# fallBz3.net
KiCad netlist of a schematic drawn in EAGLE
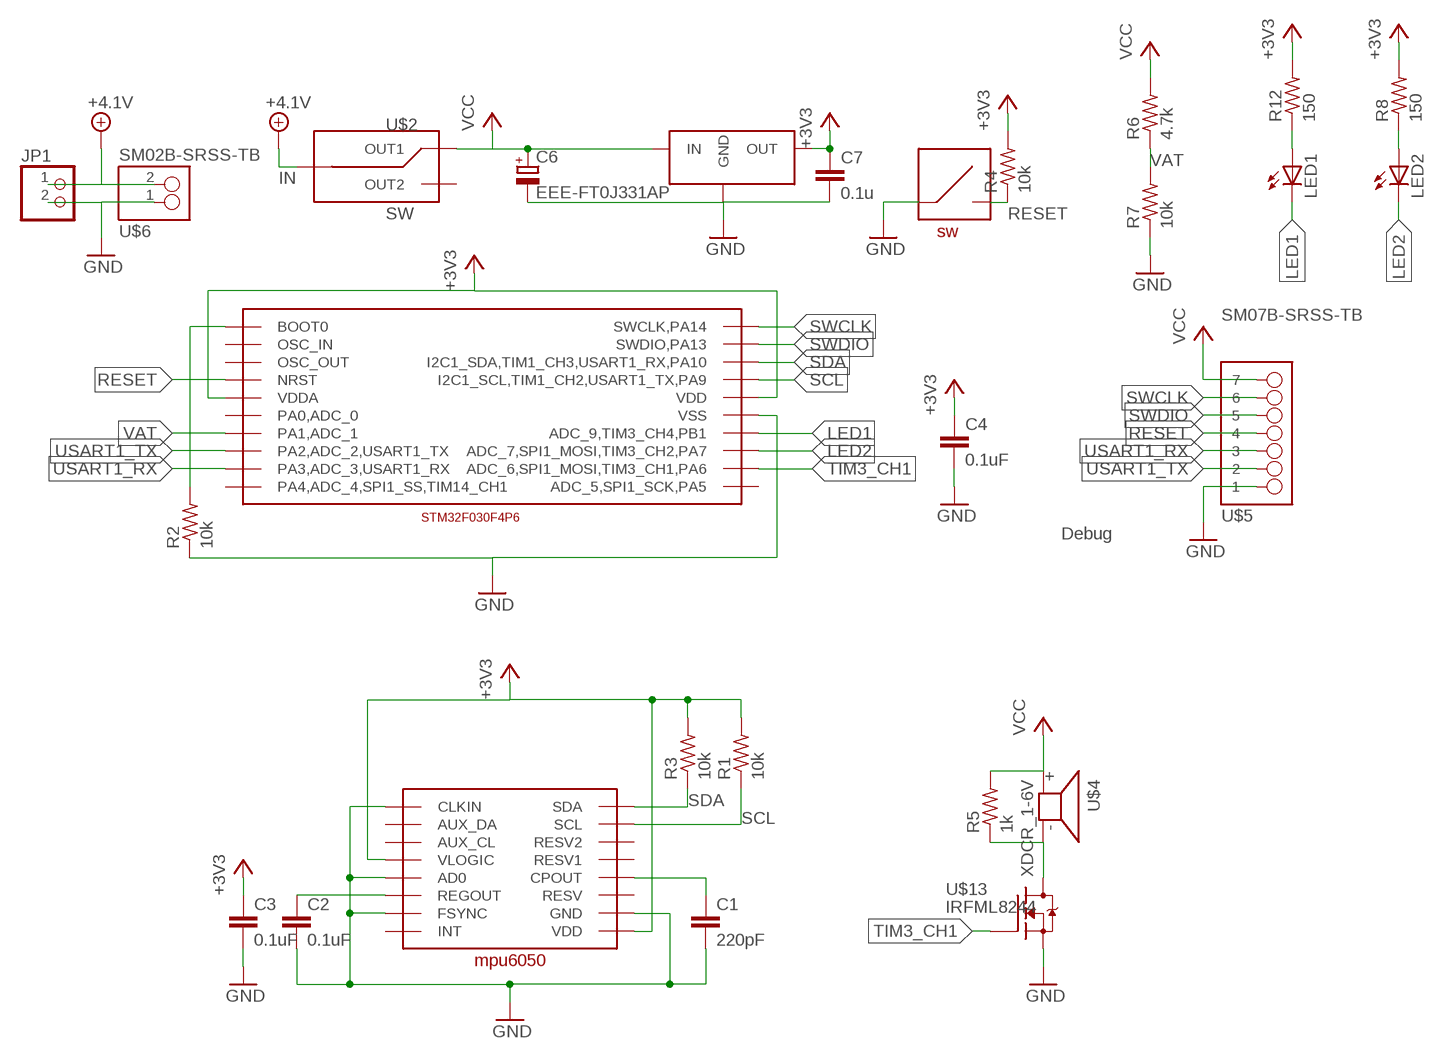
[diagram p0: schematic, sheet 1]

(export (version "E")
  (design (tool "Eeschema 10.0.6"))
  (components
    (comp (ref "C1")
      (value "220pF")
      (footprint "eagle-import:C0603K")
      (libsource (lib "eagle-import") (part "C-EUC0603K"))
    )
    (comp (ref "C2")
      (value "0.1uF")
      (footprint "eagle-import:C0603K")
      (libsource (lib "eagle-import") (part "C-EUC0603K"))
    )
    (comp (ref "C3")
      (value "0.1uF")
      (footprint "eagle-import:C0603K")
      (libsource (lib "eagle-import") (part "C-EUC0603K"))
    )
    (comp (ref "C4")
      (value "0.1uF")
      (footprint "eagle-import:C0603K")
      (libsource (lib "eagle-import") (part "C-EUC0603K"))
    )
    (comp (ref "C6")
      (value "EEE-FT0J331AP")
      (footprint "eagle-import:153CLV-0605")
      (libsource (lib "eagle-import") (part "CPOL-EU153CLV-0605"))
    )
    (comp (ref "C7")
      (value "0.1u")
      (footprint "eagle-import:C0603K")
      (libsource (lib "eagle-import") (part "C-EUC0603K"))
    )
    (comp (ref "JP1")
      (value "PINHD-1X2")
      (footprint "eagle-import:1X02")
      (libsource (lib "eagle-import") (part "PINHD-1X2"))
    )
    (comp (ref "LED1")
      (value "LEDCHIP-LED0603")
      (footprint "eagle-import:CHIP-LED0603")
      (libsource (lib "eagle-import") (part "LEDCHIP-LED0603"))
    )
    (comp (ref "LED2")
      (value "LEDCHIP-LED0603")
      (footprint "eagle-import:CHIP-LED0603")
      (libsource (lib "eagle-import") (part "LEDCHIP-LED0603"))
    )
    (comp (ref "R1")
      (value "10k")
      (footprint "eagle-import:R0603")
      (libsource (lib "eagle-import") (part "R-US_R0603"))
    )
    (comp (ref "R2")
      (value "10k")
      (footprint "eagle-import:R0603")
      (libsource (lib "eagle-import") (part "R-US_R0603"))
    )
    (comp (ref "R3")
      (value "10k")
      (footprint "eagle-import:R0603")
      (libsource (lib "eagle-import") (part "R-US_R0603"))
    )
    (comp (ref "R4")
      (value "10k")
      (footprint "eagle-import:R0603")
      (libsource (lib "eagle-import") (part "R-US_R0603"))
    )
    (comp (ref "R5")
      (value "1k")
      (footprint "eagle-import:R0603")
      (libsource (lib "eagle-import") (part "R-US_R0603"))
    )
    (comp (ref "R6")
      (value "4.7k")
      (footprint "eagle-import:R0603")
      (libsource (lib "eagle-import") (part "R-US_R0603"))
    )
    (comp (ref "R7")
      (value "10k")
      (footprint "eagle-import:R0603")
      (libsource (lib "eagle-import") (part "R-US_R0603"))
    )
    (comp (ref "R8")
      (value "150")
      (footprint "eagle-import:R0603")
      (libsource (lib "eagle-import") (part "R-US_R0603"))
    )
    (comp (ref "R12")
      (value "150")
      (footprint "eagle-import:R0603")
      (libsource (lib "eagle-import") (part "R-US_R0603"))
    )
    (comp (ref "U$1")
      (value "STM-TSSOP20")
      (footprint "eagle-import:STM-TSSOP20")
      (libsource (lib "eagle-import") (part "STM-TSSOP20"))
    )
    (comp (ref "U$2")
      (value "SW")
      (footprint "eagle-import:SS-12D00")
      (libsource (lib "eagle-import") (part "SW"))
    )
    (comp (ref "U$3")
      (value "MPU6050")
      (footprint "eagle-import:MPU6050")
      (libsource (lib "eagle-import") (part "MPU6050"))
    )
    (comp (ref "U$4")
      (value "XDCR_1-6V")
      (footprint "eagle-import:XDCR_1-6V")
      (libsource (lib "eagle-import") (part "XDCR_1-6V"))
    )
    (comp (ref "U$5")
      (value "SM07B-SRSS-TB")
      (footprint "eagle-import:SM07B-SRSS-TB")
      (libsource (lib "eagle-import") (part "SM07B-SRSS-TB"))
    )
    (comp (ref "U$6")
      (value "SM02B-SRSS-TB")
      (footprint "eagle-import:SM02B-SRSS-TB")
      (libsource (lib "eagle-import") (part "SM02B-SRSS-TB"))
    )
    (comp (ref "U$7")
      (value "KMT071-NGJ-LHS")
      (footprint "eagle-import:KMT071-NGJ-LHS")
      (libsource (lib "eagle-import") (part "KMT071-NGJ-LHS"))
    )
    (comp (ref "U$8")
      (value "AP7361-33E")
      (footprint "eagle-import:SOT223")
      (libsource (lib "eagle-import") (part "AP7361-33E"))
    )
    (comp (ref "U$13")
      (value "IRFML8244")
      (footprint "eagle-import:SOT23")
      (libsource (lib "eagle-import") (part "IRFML8244"))
    )
  )
  (nets
    (net (code "1") (name "+3V3") (class "Default")
      (node (ref "C3") (pin "1") (pinfunction "1_1") (pintype "passive"))
      (node (ref "C4") (pin "1") (pinfunction "1_1") (pintype "passive"))
      (node (ref "C7") (pin "1") (pinfunction "1_1") (pintype "passive"))
      (node (ref "R1") (pin "2") (pinfunction "2_2") (pintype "passive"))
      (node (ref "R12") (pin "2") (pinfunction "2_2") (pintype "passive"))
      (node (ref "R3") (pin "2") (pinfunction "2_2") (pintype "passive"))
      (node (ref "R4") (pin "2") (pinfunction "2_2") (pintype "passive"))
      (node (ref "R8") (pin "2") (pinfunction "2_2") (pintype "passive"))
      (node (ref "U$1") (pin "P$16") (pinfunction "VDD_P$16") (pintype "bidirectional"))
      (node (ref "U$1") (pin "P$5") (pinfunction "VDDA_P$5") (pintype "bidirectional"))
      (node (ref "U$3") (pin "VDD") (pinfunction "VDD_VDD") (pintype "bidirectional"))
      (node (ref "U$3") (pin "VLOGIC") (pinfunction "VLOGIC_VLOGIC") (pintype "bidirectional"))
      (node (ref "U$8") (pin "OUT") (pinfunction "OUT_OUT") (pintype "bidirectional"))
    )
    (net (code "2") (name "+4.1V") (class "Default")
      (node (ref "JP1") (pin "1") (pinfunction "1_1") (pintype "passive"))
      (node (ref "U$2") (pin "IN") (pinfunction "IN_IN") (pintype "bidirectional"))
      (node (ref "U$6") (pin "2") (pinfunction "P$2_2") (pintype "bidirectional"))
    )
    (net (code "3") (name "GND") (class "Default")
      (node (ref "C1") (pin "2") (pinfunction "2_2") (pintype "passive"))
      (node (ref "C2") (pin "2") (pinfunction "2_2") (pintype "passive"))
      (node (ref "C3") (pin "2") (pinfunction "2_2") (pintype "passive"))
      (node (ref "C4") (pin "2") (pinfunction "2_2") (pintype "passive"))
      (node (ref "C6") (pin "-") (pinfunction "-_-") (pintype "passive"))
      (node (ref "C7") (pin "2") (pinfunction "2_2") (pintype "passive"))
      (node (ref "JP1") (pin "2") (pinfunction "2_2") (pintype "passive"))
      (node (ref "R2") (pin "1") (pinfunction "1_1") (pintype "passive"))
      (node (ref "R7") (pin "1") (pinfunction "1_1") (pintype "passive"))
      (node (ref "U$1") (pin "P$15") (pinfunction "VSS_P$15") (pintype "bidirectional"))
      (node (ref "U$13") (pin "2") (pinfunction "S_2") (pintype "passive"))
      (node (ref "U$3") (pin "AD0") (pinfunction "AD0_AD0") (pintype "bidirectional"))
      (node (ref "U$3") (pin "CLKIN") (pinfunction "CLKIN_CLKIN") (pintype "bidirectional"))
      (node (ref "U$3") (pin "FSYNC") (pinfunction "FSYNC_FSYNC") (pintype "bidirectional"))
      (node (ref "U$3") (pin "GND") (pinfunction "GND_GND") (pintype "bidirectional"))
      (node (ref "U$5") (pin "P$1") (pinfunction "1_P$1") (pintype "bidirectional"))
      (node (ref "U$6") (pin "1") (pinfunction "P$1_1") (pintype "bidirectional"))
      (node (ref "U$7") (pin "SW0") (pinfunction "P$1_SW0") (pintype "bidirectional"))
      (node (ref "U$7") (pin "SW00") (pinfunction "P$1_SW00") (pintype "bidirectional"))
      (node (ref "U$8") (pin "GND1") (pinfunction "GND_GND1") (pintype "bidirectional"))
      (node (ref "U$8") (pin "GND2") (pinfunction "GND_GND2") (pintype "bidirectional"))
    )
    (net (code "4") (name "LED1") (class "Default")
      (node (ref "LED1") (pin "C") (pinfunction "C_C") (pintype "passive"))
      (node (ref "U$1") (pin "P$14") (pinfunction "ADC_9,TIM3_CH4,PB1_P$14") (pintype "bidirectional"))
    )
    (net (code "5") (name "LED2") (class "Default")
      (node (ref "LED2") (pin "C") (pinfunction "C_C") (pintype "passive"))
      (node (ref "U$1") (pin "P$13") (pinfunction "ADC_7,SPI1_MOSI,TIM3_CH2,PA7_P$13") (pintype "bidirectional"))
    )
    (net (code "6") (name "Net-(C1-Pad1)") (class "Default")
      (node (ref "C1") (pin "1") (pinfunction "1_1") (pintype "passive"))
      (node (ref "U$3") (pin "CPOUT") (pinfunction "CPOUT_CPOUT") (pintype "bidirectional"))
    )
    (net (code "7") (name "Net-(C2-Pad1)") (class "Default")
      (node (ref "C2") (pin "1") (pinfunction "1_1") (pintype "passive"))
      (node (ref "U$3") (pin "REGOUT") (pinfunction "REGOUT_REGOUT") (pintype "bidirectional"))
    )
    (net (code "8") (name "Net-(LED1-PadA)") (class "Default")
      (node (ref "LED1") (pin "A") (pinfunction "A_A") (pintype "passive"))
      (node (ref "R12") (pin "1") (pinfunction "1_1") (pintype "passive"))
    )
    (net (code "9") (name "Net-(LED2-PadA)") (class "Default")
      (node (ref "LED2") (pin "A") (pinfunction "A_A") (pintype "passive"))
      (node (ref "R8") (pin "1") (pinfunction "1_1") (pintype "passive"))
    )
    (net (code "10") (name "Net-(U$1-BOOT0)") (class "Default")
      (node (ref "R2") (pin "2") (pinfunction "2_2") (pintype "passive"))
      (node (ref "U$1") (pin "P$1") (pinfunction "BOOT0_P$1") (pintype "bidirectional"))
    )
    (net (code "11") (name "Net-(U$13-D)") (class "Default")
      (node (ref "R5") (pin "1") (pinfunction "1_1") (pintype "passive"))
      (node (ref "U$13") (pin "3") (pinfunction "D_3") (pintype "passive"))
      (node (ref "U$4") (pin "MINUS") (pinfunction "2_MINUS") (pintype "passive"))
    )
    (net (code "12") (name "RESET") (class "Default")
      (node (ref "R4") (pin "1") (pinfunction "1_1") (pintype "passive"))
      (node (ref "U$1") (pin "P$4") (pinfunction "NRST_P$4") (pintype "bidirectional"))
      (node (ref "U$5") (pin "P$4") (pinfunction "4_P$4") (pintype "bidirectional"))
      (node (ref "U$7") (pin "SW1") (pinfunction "P$2_SW1") (pintype "bidirectional"))
      (node (ref "U$7") (pin "SW11") (pinfunction "P$2_SW11") (pintype "bidirectional"))
    )
    (net (code "13") (name "SCL") (class "Default")
      (node (ref "R1") (pin "1") (pinfunction "1_1") (pintype "passive"))
      (node (ref "U$1") (pin "P$17") (pinfunction "I2C1_SCL,TIM1_CH2,USART1_TX,PA9_P$17") (pintype "bidirectional"))
      (node (ref "U$3") (pin "SCL") (pinfunction "SCL_SCL") (pintype "bidirectional"))
    )
    (net (code "14") (name "SDA") (class "Default")
      (node (ref "R3") (pin "1") (pinfunction "1_1") (pintype "passive"))
      (node (ref "U$1") (pin "P$18") (pinfunction "I2C1_SDA,TIM1_CH3,USART1_RX,PA10_P$18") (pintype "bidirectional"))
      (node (ref "U$3") (pin "SDA") (pinfunction "SDA_SDA") (pintype "bidirectional"))
    )
    (net (code "15") (name "SWCLK") (class "Default")
      (node (ref "U$1") (pin "P$20") (pinfunction "SWCLK,PA14_P$20") (pintype "bidirectional"))
      (node (ref "U$5") (pin "P$6") (pinfunction "6_P$6") (pintype "bidirectional"))
    )
    (net (code "16") (name "SWDIO") (class "Default")
      (node (ref "U$1") (pin "P$19") (pinfunction "SWDIO,PA13_P$19") (pintype "bidirectional"))
      (node (ref "U$5") (pin "P$5") (pinfunction "5_P$5") (pintype "bidirectional"))
    )
    (net (code "17") (name "TIM3_CH1") (class "Default")
      (node (ref "U$1") (pin "P$12") (pinfunction "ADC_6,SPI1_MOSI,TIM3_CH1,PA6_P$12") (pintype "bidirectional"))
      (node (ref "U$13") (pin "1") (pinfunction "G_1") (pintype "passive"))
    )
    (net (code "18") (name "USART1_RX") (class "Default")
      (node (ref "U$1") (pin "P$9") (pinfunction "PA3,ADC_3,USART1_RX_P$9") (pintype "bidirectional"))
      (node (ref "U$5") (pin "P$3") (pinfunction "3_P$3") (pintype "bidirectional"))
    )
    (net (code "19") (name "USART1_TX") (class "Default")
      (node (ref "U$1") (pin "P$8") (pinfunction "PA2,ADC_2,USART1_TX_P$8") (pintype "bidirectional"))
      (node (ref "U$5") (pin "P$2") (pinfunction "2_P$2") (pintype "bidirectional"))
    )
    (net (code "20") (name "VAT") (class "Default")
      (node (ref "R6") (pin "1") (pinfunction "1_1") (pintype "passive"))
      (node (ref "R7") (pin "2") (pinfunction "2_2") (pintype "passive"))
      (node (ref "U$1") (pin "P$7") (pinfunction "PA1,ADC_1_P$7") (pintype "bidirectional"))
    )
    (net (code "21") (name "VCC") (class "Default")
      (node (ref "C6") (pin "+") (pinfunction "+_+") (pintype "passive"))
      (node (ref "R5") (pin "2") (pinfunction "2_2") (pintype "passive"))
      (node (ref "R6") (pin "2") (pinfunction "2_2") (pintype "passive"))
      (node (ref "U$2") (pin "OUT1") (pinfunction "OUT1_OUT1") (pintype "bidirectional"))
      (node (ref "U$4") (pin "PLUS") (pinfunction "PLUS_PLUS") (pintype "passive"))
      (node (ref "U$5") (pin "P$7") (pinfunction "7_P$7") (pintype "bidirectional"))
      (node (ref "U$8") (pin "IN") (pinfunction "IN_IN") (pintype "bidirectional"))
    )
    (net (code "22") (name "unconnected-(U$1-ADC_5,SPI1_SCK,PA5-PadP$11)") (class "Default")
      (node (ref "U$1") (pin "P$11") (pinfunction "ADC_5,SPI1_SCK,PA5_P$11") (pintype "bidirectional"))
    )
    (net (code "23") (name "unconnected-(U$1-OSC_IN-PadP$2)") (class "Default")
      (node (ref "U$1") (pin "P$2") (pinfunction "OSC_IN_P$2") (pintype "bidirectional"))
    )
    (net (code "24") (name "unconnected-(U$1-OSC_OUT-PadP$3)") (class "Default")
      (node (ref "U$1") (pin "P$3") (pinfunction "OSC_OUT_P$3") (pintype "bidirectional"))
    )
    (net (code "25") (name "unconnected-(U$1-PA0,ADC_0-PadP$6)") (class "Default")
      (node (ref "U$1") (pin "P$6") (pinfunction "PA0,ADC_0_P$6") (pintype "bidirectional"))
    )
    (net (code "26") (name "unconnected-(U$1-PA4,ADC_4,SPI1_SS,TIM14_CH1-PadP$10)") (class "Default")
      (node (ref "U$1") (pin "P$10") (pinfunction "PA4,ADC_4,SPI1_SS,TIM14_CH1_P$10") (pintype "bidirectional"))
    )
    (net (code "27") (name "unconnected-(U$2-PadOUT2)") (class "Default")
      (node (ref "U$2") (pin "OUT2") (pinfunction "OUT2_OUT2") (pintype "bidirectional"))
    )
    (net (code "28") (name "unconnected-(U$3-PadAUX_CL)") (class "Default")
      (node (ref "U$3") (pin "AUX_CL") (pinfunction "AUX_CL_AUX_CL") (pintype "bidirectional"))
    )
    (net (code "29") (name "unconnected-(U$3-PadAUX_DA)") (class "Default")
      (node (ref "U$3") (pin "AUX_DA") (pinfunction "AUX_DA_AUX_DA") (pintype "bidirectional"))
    )
    (net (code "30") (name "unconnected-(U$3-PadINT)") (class "Default")
      (node (ref "U$3") (pin "INT") (pinfunction "INT_INT") (pintype "bidirectional"))
    )
    (net (code "31") (name "unconnected-(U$3-PadRESV)") (class "Default")
      (node (ref "U$3") (pin "RESV") (pinfunction "RESV_RESV") (pintype "bidirectional"))
    )
    (net (code "32") (name "unconnected-(U$3-PadRESV1)") (class "Default")
      (node (ref "U$3") (pin "RESV1") (pinfunction "RESV1_RESV1") (pintype "bidirectional"))
    )
    (net (code "33") (name "unconnected-(U$3-PadRESV2)") (class "Default")
      (node (ref "U$3") (pin "RESV2") (pinfunction "RESV2_RESV2") (pintype "bidirectional"))
    )
  )
)
